# LVDS.net
KiCad netlist of a schematic drawn in Altium Designer
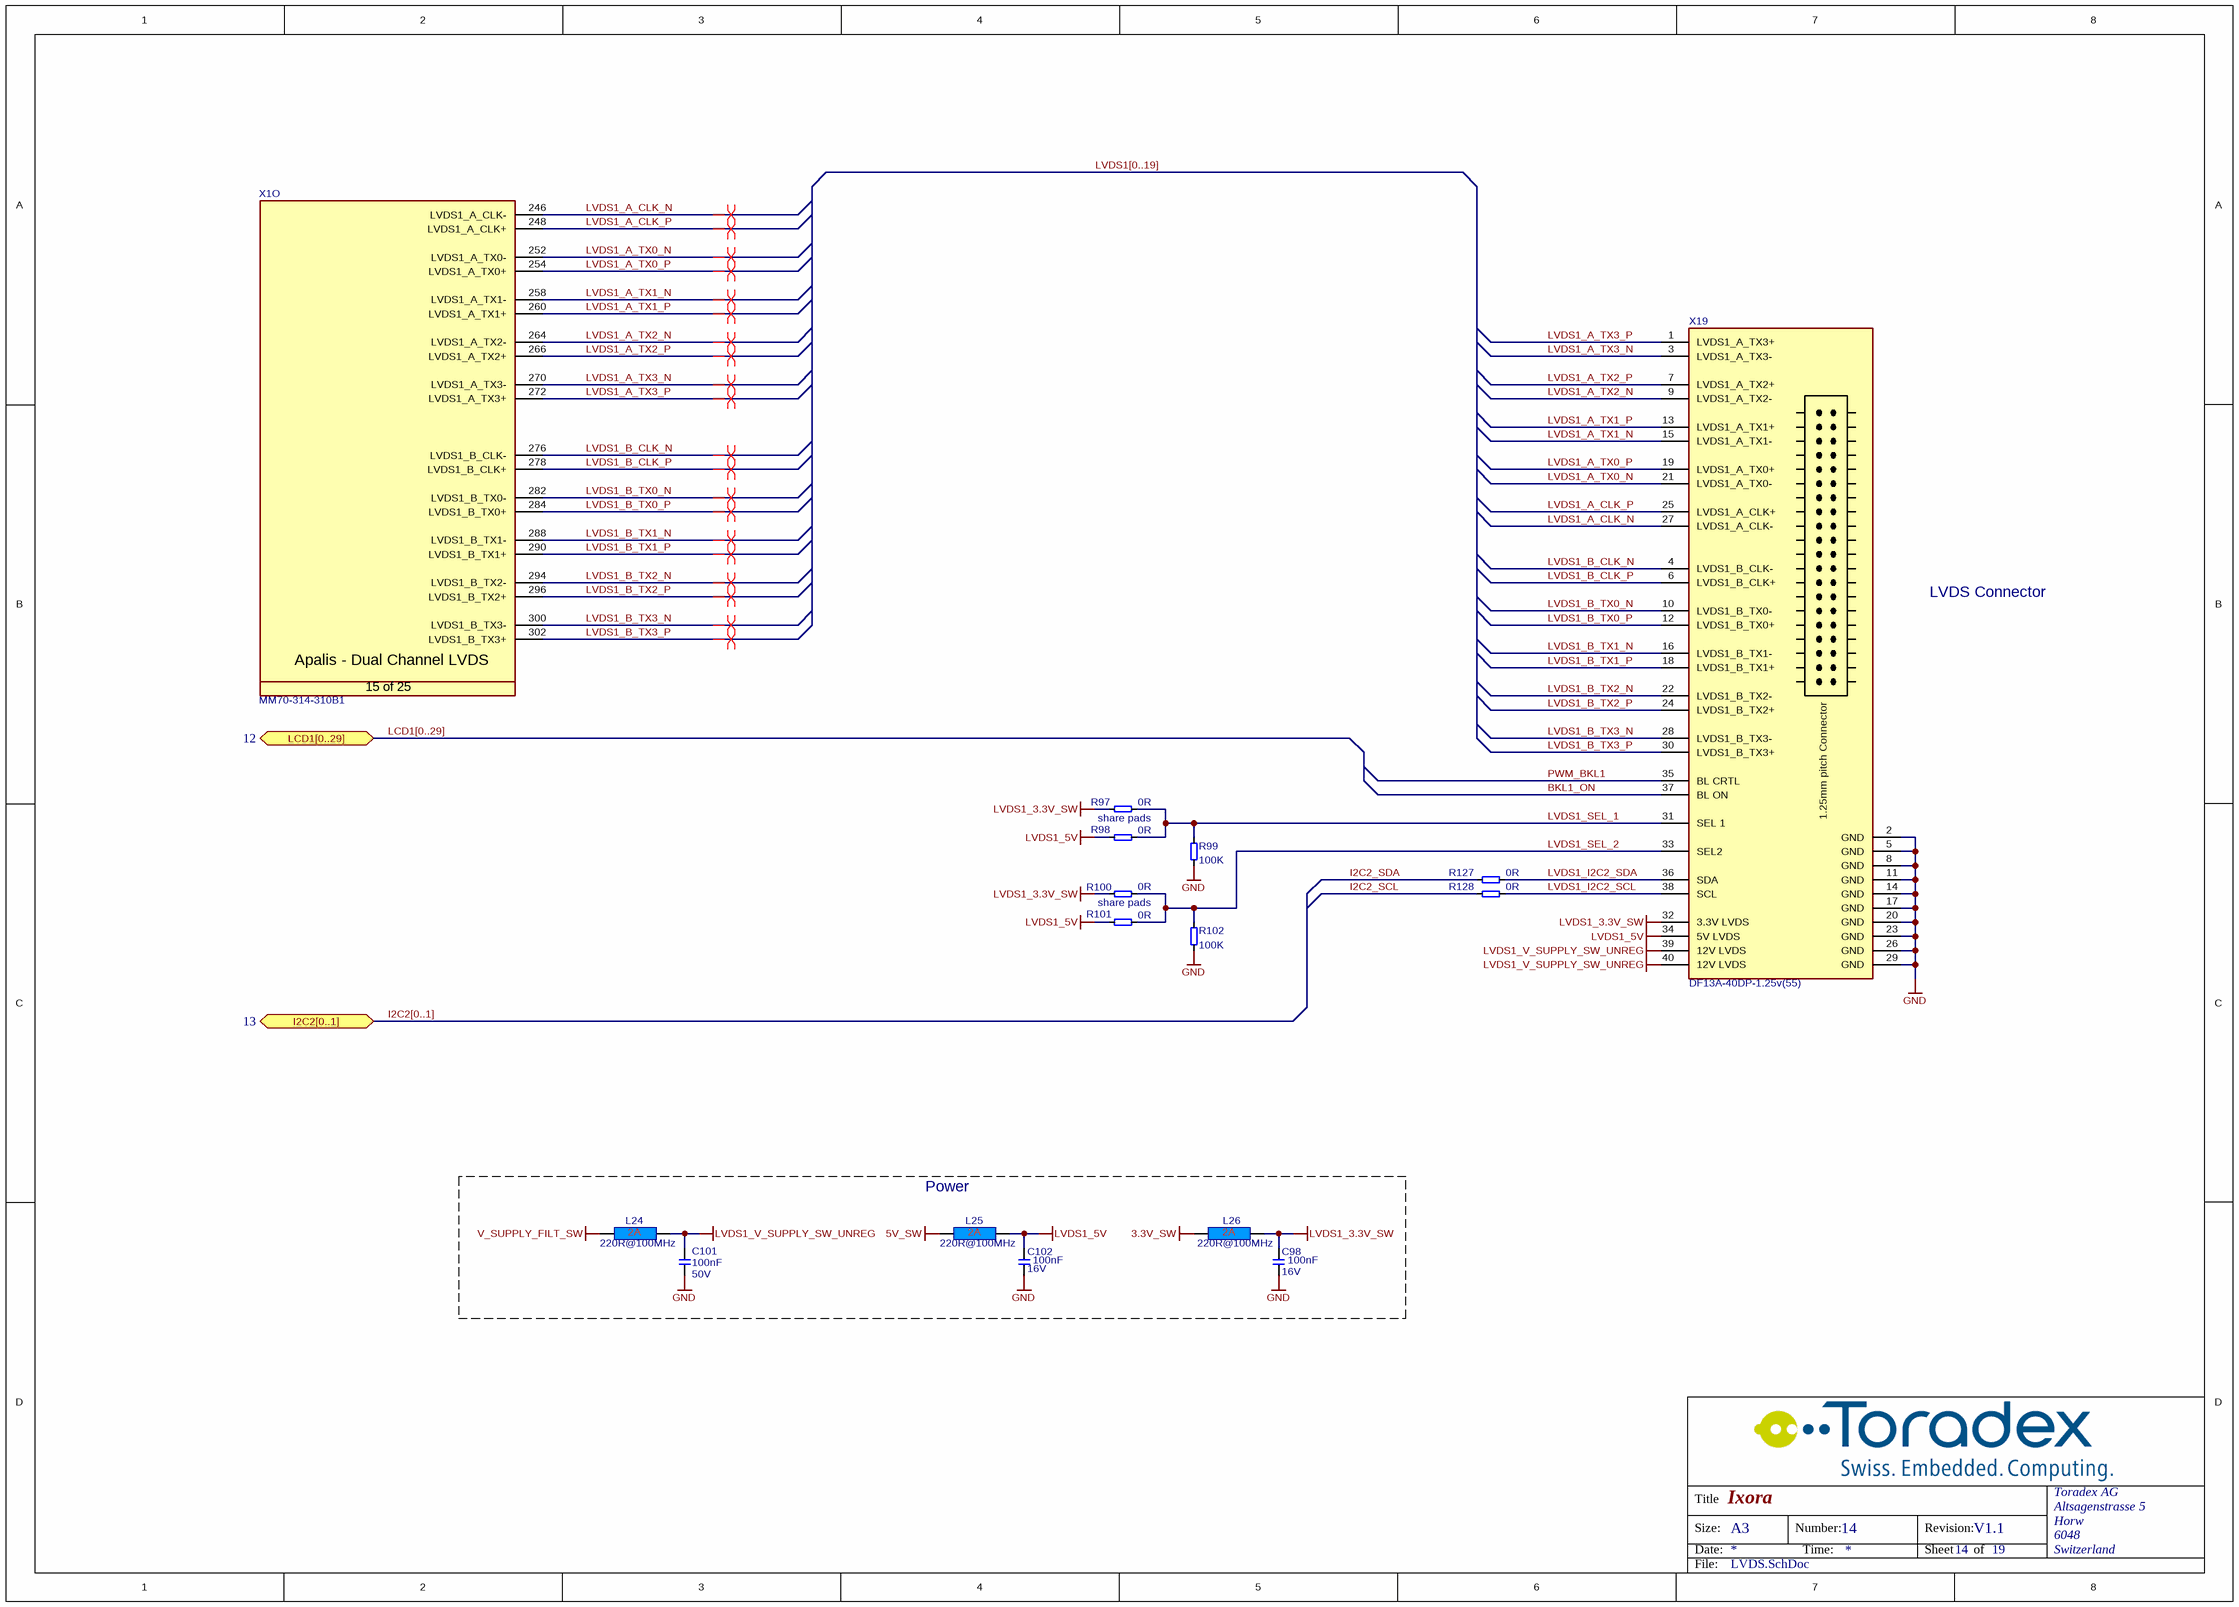
[diagram p0: LVDS.SchDoc]

(export (version "E")
  (design (tool "Eeschema 10.0.6"))
  (components
    (comp (ref "C98")
      (value "100nF")
      (footprint "CAPC1005X60N")
      (description "Capacitor Ceramic X7R 100nF 16V 10% 0402")
      (fields (field (name "TOLERANCE") "10%") (field (name "RATING") "16V"))
      (libsource (lib "Ixora") (part "C-X7R-100nF-16V-10%-0402"))
    )
    (comp (ref "C101")
      (value "100nF")
      (footprint "CAPC1005X60N")
      (description "Capacitor Ceramic X7R 100nF 50V 10% 0402")
      (fields (field (name "TOLERANCE") "10%") (field (name "RATING") "50V"))
      (libsource (lib "Ixora") (part "C-X7R-100nF-50V-10%-0402"))
    )
    (comp (ref "C102")
      (value "100nF")
      (footprint "CAPC1005X60N")
      (description "Capacitor Ceramic X7R 100nF 16V 10% 0402")
      (fields (field (name "TOLERANCE") "10%") (field (name "RATING") "16V"))
      (libsource (lib "Ixora") (part "C-X7R-100nF-16V-10%-0402"))
    )
    (comp (ref "L24")
      (value "220R@100MHz")
      (footprint "INDC1608X95N")
      (description "220R@100MHz 2A EMI FILTER")
      (fields (field (name "TOLERANCE") "25%"))
      (libsource (lib "Ixora") (part "L-220R@100MHz-2A-25%-0603"))
    )
    (comp (ref "L25")
      (value "220R@100MHz")
      (footprint "INDC1608X95N")
      (description "220R@100MHz 2A EMI FILTER")
      (fields (field (name "TOLERANCE") "25%"))
      (libsource (lib "Ixora") (part "L-220R@100MHz-2A-25%-0603"))
    )
    (comp (ref "L26")
      (value "220R@100MHz")
      (footprint "INDC1608X95N")
      (description "220R@100MHz 2A EMI FILTER")
      (fields (field (name "TOLERANCE") "25%"))
      (libsource (lib "Ixora") (part "L-220R@100MHz-2A-25%-0603"))
    )
    (comp (ref "R97")
      (value "0R")
      (footprint "T_RESC0603X30N")
      (description "Resistor 0 ohm 63mW 1% 0603")
      (fields (field (name "TOLERANCE") "1%"))
      (libsource (lib "Ixora") (part "R-0R-63mW-1%-0603"))
    )
    (comp (ref "R98")
      (value "0R")
      (footprint "T_RESC0603X30N")
      (description "Resistor 0 ohm 63mW 1% 0603")
      (fields (field (name "TOLERANCE") "1%"))
      (libsource (lib "Ixora") (part "R-0R-63mW-1%-0603"))
    )
    (comp (ref "R99")
      (value "100K")
      (footprint "RESC1005X40N")
      (description "Resistor 100 Kohm 63mW 5% 0402")
      (fields (field (name "TOLERANCE") "5%"))
      (libsource (lib "Ixora") (part "R-100KR-63mW-5%-0402"))
    )
    (comp (ref "R100")
      (value "0R")
      (footprint "T_RESC0603X30N")
      (description "Resistor 0 ohm 63mW 1% 0603")
      (fields (field (name "TOLERANCE") "1%"))
      (libsource (lib "Ixora") (part "R-0R-63mW-1%-0603"))
    )
    (comp (ref "R101")
      (value "0R")
      (footprint "T_RESC0603X30N")
      (description "Resistor 0 ohm 63mW 1% 0603")
      (fields (field (name "TOLERANCE") "1%"))
      (libsource (lib "Ixora") (part "R-0R-63mW-1%-0603"))
    )
    (comp (ref "R102")
      (value "100K")
      (footprint "RESC1005X40N")
      (description "Resistor 100 Kohm 63mW 5% 0402")
      (fields (field (name "TOLERANCE") "5%"))
      (libsource (lib "Ixora") (part "R-100KR-63mW-5%-0402"))
    )
    (comp (ref "R127")
      (value "0R")
      (footprint "T_RESC0603X30N")
      (description "Resistor 0 ohm 63mW 1% 0603")
      (fields (field (name "TOLERANCE") "1%"))
      (libsource (lib "Ixora") (part "R-0R-63mW-1%-0603"))
    )
    (comp (ref "R128")
      (value "0R")
      (footprint "T_RESC0603X30N")
      (description "Resistor 0 ohm 63mW 1% 0603")
      (fields (field (name "TOLERANCE") "1%"))
      (libsource (lib "Ixora") (part "R-0R-63mW-1%-0603"))
    )
    (comp (ref "X1")
      (value "CON-JAE-MM70-314-310B1-314-0.5mm")
      (footprint "T_JAE_MM70-314-310B1")
      (description "MXM3 Connector")
      (fields (field (name "MANUFACTURER PART NO.") "MM70-314-310B1"))
      (libsource (lib "Ixora") (part "CON-JAE-MM70-314-310B1-314-0.5mm"))
    )
    (comp (ref "X19")
      (value "CON-Hirose-DF13A-40DP-1.25v(55)-2x10-1mm")
      (footprint "T_HIROSE_DF13A-40DP-1.25V(55)")
      (description "LVDS Connector")
      (fields (field (name "MANUFACTURER PART NO.") "DF13A-40DP-1.25v(55)"))
      (libsource (lib "Ixora") (part "CON-Hirose-DF13A-40DP-1.25v(55)-2x20-1.25mm"))
    )
  )
  (nets
    (net (code "53") (name "/BKL1_ON") (class "Default")
      (node (ref "X19") (pin "37") (pinfunction "BL_ON_37") (pintype "passive"))
    )
    (net (code "55") (name "/I2C2_SCL") (class "Default")
      (node (ref "R128") (pin "1") (pinfunction "1_1") (pintype "passive"))
    )
    (net (code "56") (name "/I2C2_SDA") (class "Default")
      (node (ref "R127") (pin "1") (pinfunction "1_1") (pintype "passive"))
    )
    (net (code "59") (name "/LVDS1_A_CLK_N") (class "Default")
      (node (ref "X1") (pin "246") (pinfunction "LVDS1_A_CLK-_246") (pintype "passive"))
      (node (ref "X19") (pin "27") (pinfunction "LVDS1_A_CLK-_27") (pintype "passive"))
    )
    (net (code "60") (name "/LVDS1_A_CLK_P") (class "Default")
      (node (ref "X1") (pin "248") (pinfunction "LVDS1_A_CLK+_248") (pintype "passive"))
      (node (ref "X19") (pin "25") (pinfunction "LVDS1_A_CLK+_25") (pintype "passive"))
    )
    (net (code "61") (name "/LVDS1_A_TX0_N") (class "Default")
      (node (ref "X1") (pin "252") (pinfunction "LVDS1_A_TX0-_252") (pintype "passive"))
      (node (ref "X19") (pin "21") (pinfunction "LVDS1_A_TX0-_21") (pintype "passive"))
    )
    (net (code "62") (name "/LVDS1_A_TX0_P") (class "Default")
      (node (ref "X1") (pin "254") (pinfunction "LVDS1_A_TX0+_254") (pintype "passive"))
      (node (ref "X19") (pin "19") (pinfunction "LVDS1_A_TX0+_19") (pintype "passive"))
    )
    (net (code "63") (name "/LVDS1_A_TX1_N") (class "Default")
      (node (ref "X1") (pin "258") (pinfunction "LVDS1_A_TX1-_258") (pintype "passive"))
      (node (ref "X19") (pin "15") (pinfunction "LVDS1_A_TX1-_15") (pintype "passive"))
    )
    (net (code "64") (name "/LVDS1_A_TX1_P") (class "Default")
      (node (ref "X1") (pin "260") (pinfunction "LVDS1_A_TX1+_260") (pintype "passive"))
      (node (ref "X19") (pin "13") (pinfunction "LVDS1_A_TX1+_13") (pintype "passive"))
    )
    (net (code "65") (name "/LVDS1_A_TX2_N") (class "Default")
      (node (ref "X1") (pin "264") (pinfunction "LVDS1_A_TX2-_264") (pintype "passive"))
      (node (ref "X19") (pin "9") (pinfunction "LVDS1_A_TX2-_9") (pintype "passive"))
    )
    (net (code "66") (name "/LVDS1_A_TX2_P") (class "Default")
      (node (ref "X1") (pin "266") (pinfunction "LVDS1_A_TX2+_266") (pintype "passive"))
      (node (ref "X19") (pin "7") (pinfunction "LVDS1_A_TX2+_7") (pintype "passive"))
    )
    (net (code "67") (name "/LVDS1_A_TX3_N") (class "Default")
      (node (ref "X1") (pin "270") (pinfunction "LVDS1_A_TX3-_270") (pintype "passive"))
      (node (ref "X19") (pin "3") (pinfunction "LVDS1_A_TX3-_3") (pintype "passive"))
    )
    (net (code "68") (name "/LVDS1_A_TX3_P") (class "Default")
      (node (ref "X1") (pin "272") (pinfunction "LVDS1_A_TX3+_272") (pintype "passive"))
      (node (ref "X19") (pin "1") (pinfunction "LVDS1_A_TX3+_1") (pintype "passive"))
    )
    (net (code "69") (name "/LVDS1_B_CLK_N") (class "Default")
      (node (ref "X1") (pin "276") (pinfunction "LVDS1_B_CLK-_276") (pintype "passive"))
      (node (ref "X19") (pin "4") (pinfunction "LVDS1_B_CLK-_4") (pintype "passive"))
    )
    (net (code "70") (name "/LVDS1_B_CLK_P") (class "Default")
      (node (ref "X1") (pin "278") (pinfunction "LVDS1_B_CLK+_278") (pintype "passive"))
      (node (ref "X19") (pin "6") (pinfunction "LVDS1_B_CLK+_6") (pintype "passive"))
    )
    (net (code "71") (name "/LVDS1_B_TX0_N") (class "Default")
      (node (ref "X1") (pin "282") (pinfunction "LVDS1_B_TX0-_282") (pintype "passive"))
      (node (ref "X19") (pin "10") (pinfunction "LVDS1_B_TX0-_10") (pintype "passive"))
    )
    (net (code "72") (name "/LVDS1_B_TX0_P") (class "Default")
      (node (ref "X1") (pin "284") (pinfunction "LVDS1_B_TX0+_284") (pintype "passive"))
      (node (ref "X19") (pin "12") (pinfunction "LVDS1_B_TX0+_12") (pintype "passive"))
    )
    (net (code "73") (name "/LVDS1_B_TX1_N") (class "Default")
      (node (ref "X1") (pin "288") (pinfunction "LVDS1_B_TX1-_288") (pintype "passive"))
      (node (ref "X19") (pin "16") (pinfunction "LVDS1_B_TX1-_16") (pintype "passive"))
    )
    (net (code "74") (name "/LVDS1_B_TX1_P") (class "Default")
      (node (ref "X1") (pin "290") (pinfunction "LVDS1_B_TX1+_290") (pintype "passive"))
      (node (ref "X19") (pin "18") (pinfunction "LVDS1_B_TX1+_18") (pintype "passive"))
    )
    (net (code "75") (name "/LVDS1_B_TX2_N") (class "Default")
      (node (ref "X1") (pin "294") (pinfunction "LVDS1_B_TX2-_294") (pintype "passive"))
      (node (ref "X19") (pin "22") (pinfunction "LVDS1_B_TX2-_22") (pintype "passive"))
    )
    (net (code "76") (name "/LVDS1_B_TX2_P") (class "Default")
      (node (ref "X1") (pin "296") (pinfunction "LVDS1_B_TX2+_296") (pintype "passive"))
      (node (ref "X19") (pin "24") (pinfunction "LVDS1_B_TX2+_24") (pintype "passive"))
    )
    (net (code "77") (name "/LVDS1_B_TX3_N") (class "Default")
      (node (ref "X1") (pin "300") (pinfunction "LVDS1_B_TX3-_300") (pintype "passive"))
      (node (ref "X19") (pin "28") (pinfunction "LVDS1_B_TX3-_28") (pintype "passive"))
    )
    (net (code "78") (name "/LVDS1_B_TX3_P") (class "Default")
      (node (ref "X1") (pin "302") (pinfunction "LVDS1_B_TX3+_302") (pintype "passive"))
      (node (ref "X19") (pin "30") (pinfunction "LVDS1_B_TX3+_30") (pintype "passive"))
    )
    (net (code "79") (name "/LVDS1_I2C2_SCL") (class "Default")
      (node (ref "R128") (pin "2") (pinfunction "2_2") (pintype "passive"))
      (node (ref "X19") (pin "38") (pinfunction "SCL_38") (pintype "passive"))
    )
    (net (code "80") (name "/LVDS1_I2C2_SDA") (class "Default")
      (node (ref "R127") (pin "2") (pinfunction "2_2") (pintype "passive"))
      (node (ref "X19") (pin "36") (pinfunction "SDA_36") (pintype "passive"))
    )
    (net (code "81") (name "/LVDS1_SEL_1") (class "Default")
      (node (ref "R97") (pin "2") (pinfunction "2_2") (pintype "passive"))
      (node (ref "R98") (pin "2") (pinfunction "2_2") (pintype "passive"))
      (node (ref "R99") (pin "2") (pinfunction "2_2") (pintype "passive"))
      (node (ref "X19") (pin "31") (pinfunction "SEL_1_31") (pintype "passive"))
    )
    (net (code "82") (name "/LVDS1_SEL_2") (class "Default")
      (node (ref "R100") (pin "2") (pinfunction "2_2") (pintype "passive"))
      (node (ref "R101") (pin "2") (pinfunction "2_2") (pintype "passive"))
      (node (ref "R102") (pin "2") (pinfunction "2_2") (pintype "passive"))
      (node (ref "X19") (pin "33") (pinfunction "SEL2_33") (pintype "passive"))
    )
    (net (code "83") (name "/PWM_BKL1") (class "Default")
      (node (ref "X19") (pin "35") (pinfunction "BL_CRTL_35") (pintype "passive"))
    )
    (net (code "84") (name "3.3V_SW") (class "Default")
      (node (ref "L26") (pin "1") (pinfunction "1_1") (pintype "passive"))
    )
    (net (code "85") (name "5V_SW") (class "Default")
      (node (ref "L25") (pin "1") (pinfunction "1_1") (pintype "passive"))
    )
    (net (code "86") (name "GND") (class "Default")
      (node (ref "C101") (pin "1") (pinfunction "1_1") (pintype "passive"))
      (node (ref "C102") (pin "1") (pinfunction "1_1") (pintype "passive"))
      (node (ref "C98") (pin "1") (pinfunction "1_1") (pintype "passive"))
      (node (ref "R102") (pin "1") (pinfunction "1_1") (pintype "passive"))
      (node (ref "R99") (pin "1") (pinfunction "1_1") (pintype "passive"))
      (node (ref "X19") (pin "11") (pinfunction "GND_11") (pintype "passive"))
      (node (ref "X19") (pin "14") (pinfunction "GND_14") (pintype "passive"))
      (node (ref "X19") (pin "17") (pinfunction "GND_17") (pintype "passive"))
      (node (ref "X19") (pin "2") (pinfunction "GND_2") (pintype "passive"))
      (node (ref "X19") (pin "20") (pinfunction "GND_20") (pintype "passive"))
      (node (ref "X19") (pin "23") (pinfunction "GND_23") (pintype "passive"))
      (node (ref "X19") (pin "26") (pinfunction "GND_26") (pintype "passive"))
      (node (ref "X19") (pin "29") (pinfunction "GND_29") (pintype "passive"))
      (node (ref "X19") (pin "5") (pinfunction "GND_5") (pintype "passive"))
      (node (ref "X19") (pin "8") (pinfunction "GND_8") (pintype "passive"))
    )
    (net (code "87") (name "LVDS1_3.3V_SW") (class "Default")
      (node (ref "C98") (pin "2") (pinfunction "2_2") (pintype "passive"))
      (node (ref "L26") (pin "2") (pinfunction "2_2") (pintype "passive"))
      (node (ref "R100") (pin "1") (pinfunction "1_1") (pintype "passive"))
      (node (ref "R97") (pin "1") (pinfunction "1_1") (pintype "passive"))
      (node (ref "X19") (pin "32") (pinfunction "3.3V_LVDS_32") (pintype "passive"))
    )
    (net (code "88") (name "LVDS1_5V") (class "Default")
      (node (ref "C102") (pin "2") (pinfunction "2_2") (pintype "passive"))
      (node (ref "L25") (pin "2") (pinfunction "2_2") (pintype "passive"))
      (node (ref "R101") (pin "1") (pinfunction "1_1") (pintype "passive"))
      (node (ref "R98") (pin "1") (pinfunction "1_1") (pintype "passive"))
      (node (ref "X19") (pin "34") (pinfunction "5V_LVDS_34") (pintype "passive"))
    )
    (net (code "89") (name "LVDS1_V_SUPPLY_SW_UNREG") (class "Default")
      (node (ref "C101") (pin "2") (pinfunction "2_2") (pintype "passive"))
      (node (ref "L24") (pin "2") (pinfunction "2_2") (pintype "passive"))
      (node (ref "X19") (pin "39") (pinfunction "12V_LVDS_39") (pintype "passive"))
      (node (ref "X19") (pin "40") (pinfunction "12V_LVDS_40") (pintype "passive"))
    )
    (net (code "90") (name "V_SUPPLY_FILT_SW") (class "Default")
      (node (ref "L24") (pin "1") (pinfunction "1_1") (pintype "passive"))
    )
  )
)
